# buck.net
KiCad netlist of a schematic drawn in Altium Designer
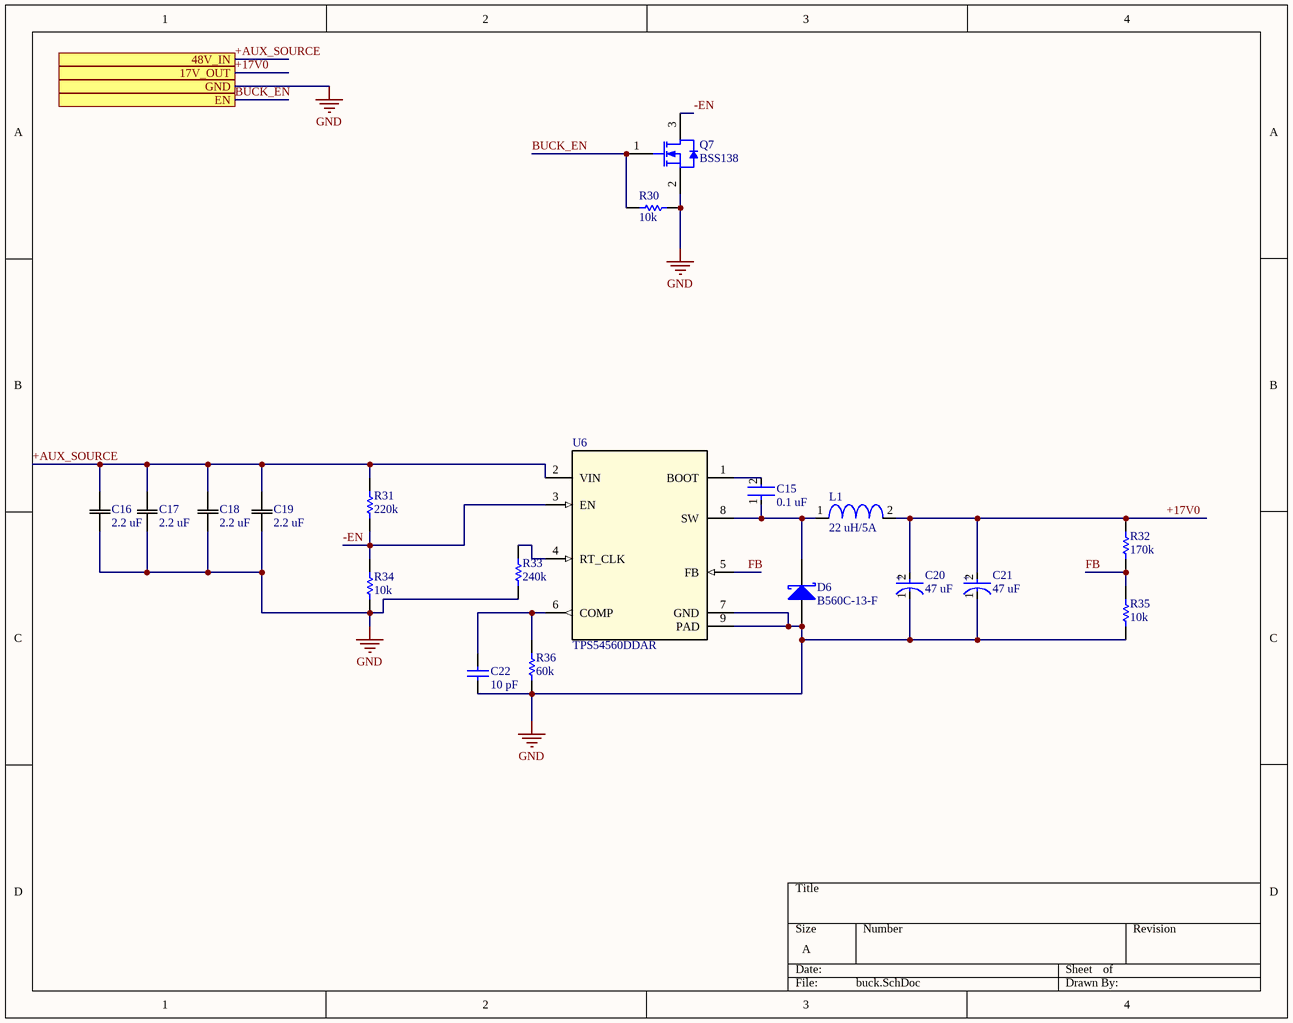
[diagram p0: buck.SchDoc]

(export (version "E")
  (design (tool "Eeschema 10.0.6"))
  (components
    (comp (ref "C15")
      (value "0.1 uF")
      (footprint "FP-CC0603-DA-MFG")
      (description "CAP CER 0.1UF 16V X7R 0603")
      (fields
        (field (name "OCTOPART") "https://octopart.com/cc0603krx7r7bb104-yageo-192941")
        (field (name "TOLERANCE") "0.1")
      )
      (libsource (lib "Altium Content Vault") (part "11868f565c42a9108669ba33697ecf6"))
    )
    (comp (ref "C16")
      (value "2.2 uF")
      (footprint "CAP_GMC32_2.8H_CCE")
      (description "GMC32X7R225K100NT-CAP CER 2.2UF 100V X7R 1210")
      (fields
        (field (name "MANUFACTURER_PART_NUMBER") "GMC32X7R225K100NT")
        (field (name "COPYRIGHT") "Copyright (C) 2023 Ultra Librarian. All rights reserved.")
      )
      (libsource (lib "GMC32X7R225K100NT") (part "GMC32X7R225K100NT"))
    )
    (comp (ref "C17")
      (value "2.2 uF")
      (footprint "CAP_GMC32_2.8H_CCE")
      (description "GMC32X7R225K100NT-CAP CER 2.2UF 100V X7R 1210")
      (fields
        (field (name "MANUFACTURER_PART_NUMBER") "GMC32X7R225K100NT")
        (field (name "COPYRIGHT") "Copyright (C) 2023 Ultra Librarian. All rights reserved.")
      )
      (libsource (lib "GMC32X7R225K100NT") (part "GMC32X7R225K100NT"))
    )
    (comp (ref "C18")
      (value "2.2 uF")
      (footprint "CAP_GMC32_2.8H_CCE")
      (description "GMC32X7R225K100NT-CAP CER 2.2UF 100V X7R 1210")
      (fields
        (field (name "MANUFACTURER_PART_NUMBER") "GMC32X7R225K100NT")
        (field (name "COPYRIGHT") "Copyright (C) 2023 Ultra Librarian. All rights reserved.")
      )
      (libsource (lib "GMC32X7R225K100NT") (part "GMC32X7R225K100NT"))
    )
    (comp (ref "C19")
      (value "2.2 uF")
      (footprint "CAP_GMC32_2.8H_CCE")
      (description "GMC32X7R225K100NT-CAP CER 2.2UF 100V X7R 1210")
      (fields
        (field (name "MANUFACTURER_PART_NUMBER") "GMC32X7R225K100NT")
        (field (name "COPYRIGHT") "Copyright (C) 2023 Ultra Librarian. All rights reserved.")
      )
      (libsource (lib "GMC32X7R225K100NT") (part "GMC32X7R225K100NT"))
    )
    (comp (ref "C20")
      (value "47 uF")
      (footprint "FP-FPD-MFG")
      (description "CAP ALUM 47UF 20% 35V SMD")
      (fields (field (name "TOLERANCE") "20%") (field (name "VOLTAGE") "35V"))
      (libsource (lib "Altium Content Vault") (part "cf48714ba7e38822c1575c7ec0b6d1f"))
    )
    (comp (ref "C21")
      (value "47 uF")
      (footprint "FP-FPD-MFG")
      (description "CAP ALUM 47UF 20% 35V SMD")
      (fields (field (name "TOLERANCE") "20%") (field (name "VOLTAGE") "35V"))
      (libsource (lib "Altium Content Vault") (part "cf48714ba7e38822c1575c7ec0b6d1f"))
    )
    (comp (ref "C22")
      (value "10 pF")
      (footprint "CAPC1608X90X35LL10T15")
      (description "Multilayer Ceramic Capacitor, 10 pF, 50 V, ± 5%, C0G (NP0), 0603 [1608 Metric]")
      (fields (field (name "PART NUMBER") "GRM1885C1H100JA01D") (field (name "MANUFACTURER") "Murata"))
      (libsource (lib "Altium Content Vault") (part "CAP"))
    )
    (comp (ref "D6")
      (value "B560C-13-F")
      (footprint "DIOD-B5X0C-2_M")
      (description "Schottky Barrier Rectifier, 5 A, 60 V, -55 to 125 degC, 2-Pin SMD, RoHS, Tape and Reel")
      (fields (field (name "MANUFACTURER") "DiodesIncorporated"))
      (libsource (lib "Altium Content Vault") (part "DSKY-KA-2"))
    )
    (comp (ref "L1")
      (value "22 uH/5A")
      (footprint "SMPI06050-220M")
      (description "INDUCTOR POWER 22UH 7.7X6.6MM SMD")
      (libsource (lib "Schlib1") (part "SMPI06050-220M"))
    )
    (comp (ref "Q7")
      (value "BSS138")
      (footprint "FAIR-SOT23-3_V")
      (fields (field (name "MANUFACTURER") "Fairchild") (field (name "POWER") "360mW"))
      (libsource (lib "İtü Rov") (part "NEMOS-GSD-3"))
    )
    (comp (ref "R30")
      (value "10k")
      (footprint "RESC1609X50X30NL8T20")
      (description "Chip Resistor, 10 KOhm, +/- 1%, 100 mW, -55 to 155 degC, 0603 (1608 Metric), RoHS, Tape and Reel")
      (fields (field (name "MANUFACTURER") "Vishay Semiconductor"))
      (libsource (lib "Altium Content Vault") (part "RES-2"))
    )
    (comp (ref "R31")
      (value "220k")
      (footprint "RESC1609X50X30NL8T20")
      (description "Chip Resistor, 10 KOhm, +/- 1%, 100 mW, -55 to 155 degC, 0603 (1608 Metric), RoHS, Tape and Reel")
      (fields (field (name "MANUFACTURER") "Vishay Semiconductor"))
      (libsource (lib "Altium Content Vault") (part "RES-2"))
    )
    (comp (ref "R32")
      (value "170k")
      (footprint "RESC1609X50X30NL8T20")
      (description "Chip Resistor, 10 KOhm, +/- 1%, 100 mW, -55 to 155 degC, 0603 (1608 Metric), RoHS, Tape and Reel")
      (fields (field (name "MANUFACTURER") "Vishay Semiconductor"))
      (libsource (lib "Altium Content Vault") (part "RES-2"))
    )
    (comp (ref "R33")
      (value "240k")
      (footprint "RESC1609X50X30NL8T20")
      (description "Chip Resistor, 10 KOhm, +/- 1%, 100 mW, -55 to 155 degC, 0603 (1608 Metric), RoHS, Tape and Reel")
      (fields (field (name "MANUFACTURER") "Vishay Semiconductor"))
      (libsource (lib "Altium Content Vault") (part "RES-2"))
    )
    (comp (ref "R34")
      (value "10k")
      (footprint "RESC1609X50X30NL8T20")
      (description "Chip Resistor, 10 KOhm, +/- 1%, 100 mW, -55 to 155 degC, 0603 (1608 Metric), RoHS, Tape and Reel")
      (fields (field (name "MANUFACTURER") "Vishay Semiconductor"))
      (libsource (lib "Altium Content Vault") (part "RES-2"))
    )
    (comp (ref "R35")
      (value "10k")
      (footprint "RESC1609X50X30NL8T20")
      (description "Chip Resistor, 10 KOhm, +/- 1%, 100 mW, -55 to 155 degC, 0603 (1608 Metric), RoHS, Tape and Reel")
      (fields (field (name "MANUFACTURER") "Vishay Semiconductor"))
      (libsource (lib "Altium Content Vault") (part "RES-2"))
    )
    (comp (ref "R36")
      (value "60k")
      (footprint "RESC1609X50X30NL8T20")
      (description "Chip Resistor, 10 KOhm, +/- 1%, 100 mW, -55 to 155 degC, 0603 (1608 Metric), RoHS, Tape and Reel")
      (fields (field (name "MANUFACTURER") "Vishay Semiconductor"))
      (libsource (lib "Altium Content Vault") (part "RES-2"))
    )
    (comp (ref "U6")
      (value "TPS54560DDAR")
      (footprint "DDA0008E_N")
      (description "No Description Available")
      (fields (field (name "COPYRIGHT") "Copyright (C) 2023 Ultra Librarian. All rights reserved."))
      (libsource (lib "TPS54560DDAR") (part "TPS54560DDAR"))
    )
  )
  (nets
    (net (code "1") (name "/+17V0") (class "Default")
      (node (ref "C20") (pin "2") (pinfunction "A_2") (pintype "passive"))
      (node (ref "C21") (pin "2") (pinfunction "A_2") (pintype "passive"))
      (node (ref "L1") (pin "2") (pinfunction "2_2") (pintype "passive"))
      (node (ref "R32") (pin "2") (pinfunction "2_2") (pintype "passive"))
    )
    (net (code "2") (name "/+AUX_SOURCE") (class "Default")
      (node (ref "C16") (pin "2") (pinfunction "2_2") (pintype "passive"))
      (node (ref "C17") (pin "2") (pinfunction "2_2") (pintype "passive"))
      (node (ref "C18") (pin "2") (pinfunction "2_2") (pintype "passive"))
      (node (ref "C19") (pin "2") (pinfunction "2_2") (pintype "passive"))
      (node (ref "R31") (pin "2") (pinfunction "2_2") (pintype "passive"))
      (node (ref "U6") (pin "2") (pinfunction "VIN_2") (pintype "power_in"))
    )
    (net (code "3") (name "/-EN") (class "Default")
      (node (ref "Q7") (pin "3") (pinfunction "D_3") (pintype "passive"))
      (node (ref "R31") (pin "1") (pinfunction "1_1") (pintype "passive"))
      (node (ref "R34") (pin "2") (pinfunction "2_2") (pintype "passive"))
      (node (ref "U6") (pin "3") (pinfunction "EN_3") (pintype "input"))
    )
    (net (code "4") (name "/BUCK_EN") (class "Default")
      (node (ref "Q7") (pin "1") (pinfunction "G_1") (pintype "passive"))
      (node (ref "R30") (pin "2") (pinfunction "2_2") (pintype "passive"))
    )
    (net (code "5") (name "/FB") (class "Default")
      (node (ref "R32") (pin "1") (pinfunction "1_1") (pintype "passive"))
      (node (ref "R35") (pin "2") (pinfunction "2_2") (pintype "passive"))
      (node (ref "U6") (pin "5") (pinfunction "FB_5") (pintype "input"))
    )
    (net (code "6") (name "GND") (class "Default")
      (node (ref "C16") (pin "1") (pinfunction "1_1") (pintype "passive"))
      (node (ref "C17") (pin "1") (pinfunction "1_1") (pintype "passive"))
      (node (ref "C18") (pin "1") (pinfunction "1_1") (pintype "passive"))
      (node (ref "C19") (pin "1") (pinfunction "1_1") (pintype "passive"))
      (node (ref "C20") (pin "1") (pinfunction "C_1") (pintype "passive"))
      (node (ref "C21") (pin "1") (pinfunction "C_1") (pintype "passive"))
      (node (ref "C22") (pin "1") (pinfunction "1_1") (pintype "passive"))
      (node (ref "D6") (pin "2") (pinfunction "A_2") (pintype "passive"))
      (node (ref "Q7") (pin "2") (pinfunction "S_2") (pintype "passive"))
      (node (ref "R30") (pin "1") (pinfunction "1_1") (pintype "passive"))
      (node (ref "R33") (pin "1") (pinfunction "1_1") (pintype "passive"))
      (node (ref "R34") (pin "1") (pinfunction "1_1") (pintype "passive"))
      (node (ref "R35") (pin "1") (pinfunction "1_1") (pintype "passive"))
      (node (ref "R36") (pin "1") (pinfunction "1_1") (pintype "passive"))
      (node (ref "U6") (pin "7") (pinfunction "GND_7") (pintype "power_in"))
      (node (ref "U6") (pin "9") (pinfunction "PAD_9") (pintype "power_in"))
    )
    (net (code "7") (name "Net-(D6-K)") (class "Default")
      (node (ref "C15") (pin "1") (pinfunction "1_1") (pintype "passive"))
      (node (ref "D6") (pin "1") (pinfunction "K_1") (pintype "passive"))
      (node (ref "L1") (pin "1") (pinfunction "1_1") (pintype "passive"))
      (node (ref "U6") (pin "8") (pinfunction "SW_8") (pintype "power_in"))
    )
    (net (code "8") (name "Net-(U6-BOOT)") (class "Default")
      (node (ref "C15") (pin "2") (pinfunction "2_2") (pintype "passive"))
      (node (ref "U6") (pin "1") (pinfunction "BOOT_1") (pintype "power_in"))
    )
    (net (code "9") (name "Net-(U6-COMP)") (class "Default")
      (node (ref "C22") (pin "2") (pinfunction "2_2") (pintype "passive"))
      (node (ref "R36") (pin "2") (pinfunction "2_2") (pintype "passive"))
      (node (ref "U6") (pin "6") (pinfunction "COMP_6") (pintype "output"))
    )
    (net (code "10") (name "Net-(U6-RT_CLK)") (class "Default")
      (node (ref "R33") (pin "2") (pinfunction "2_2") (pintype "passive"))
      (node (ref "U6") (pin "4") (pinfunction "RT_CLK_4") (pintype "input"))
    )
  )
)
